# BW1097_TopLevel.net
KiCad netlist of a schematic drawn in Altium Designer
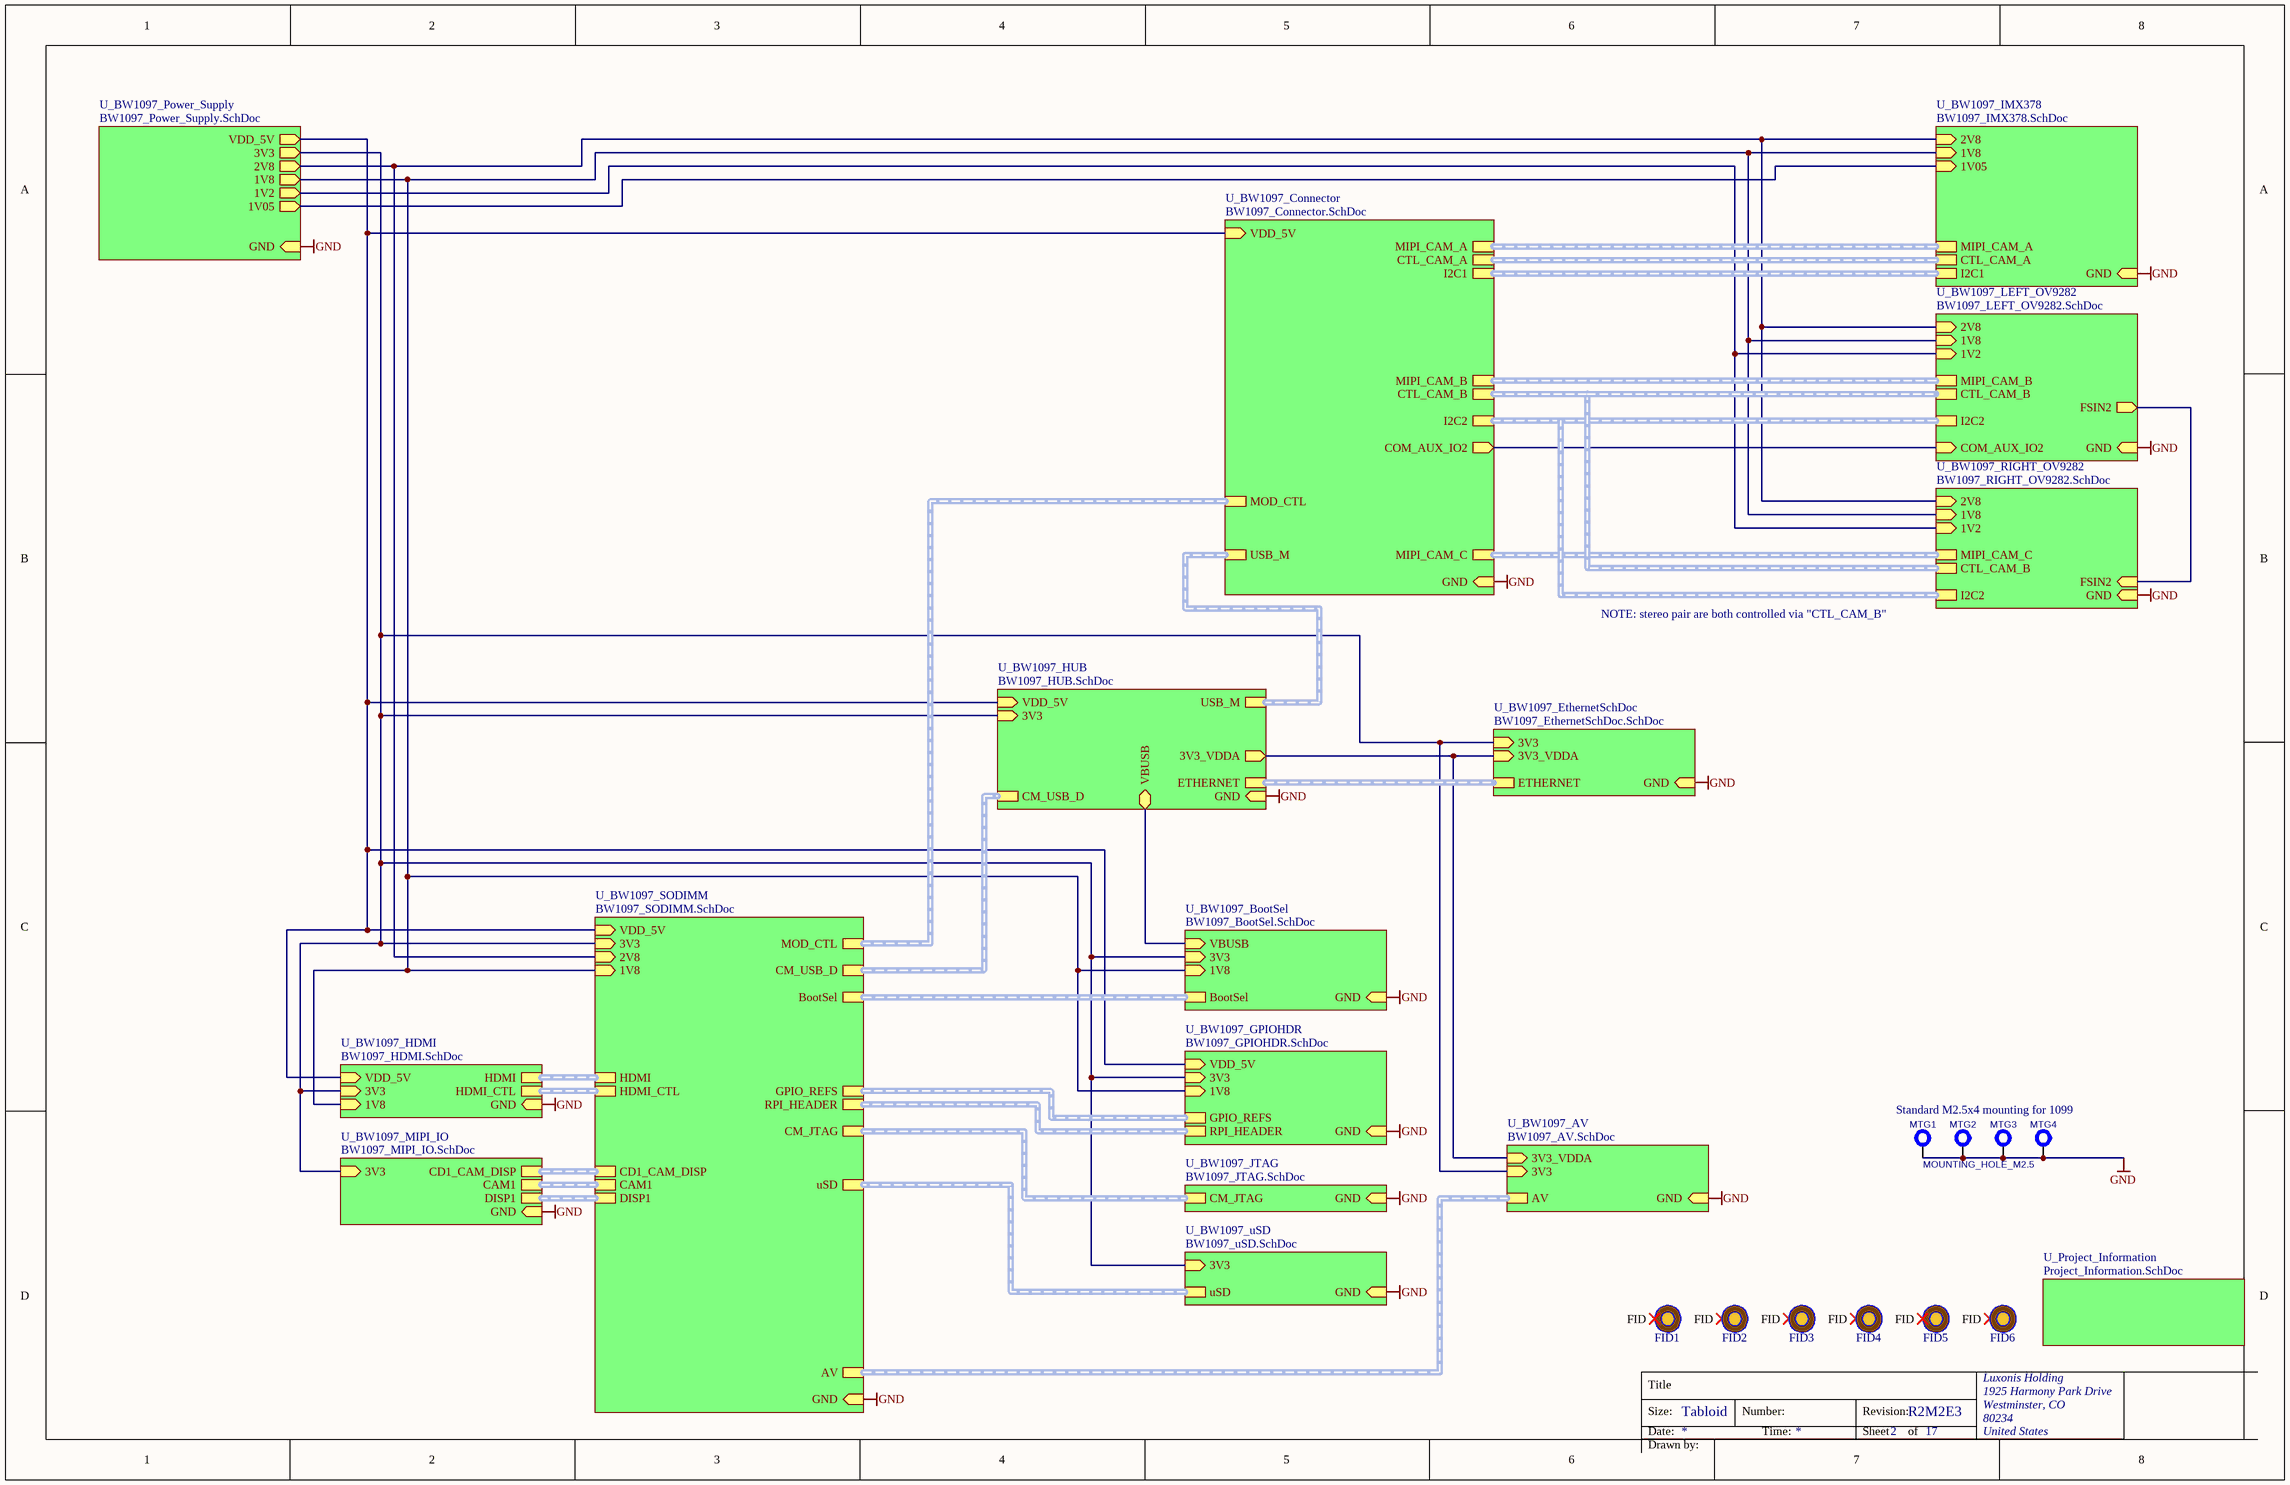
[diagram p0: BW1097_TopLevel.SchDoc]

(export (version "E")
  (design (tool "Eeschema 10.0.6"))
  (components
    (comp (ref "FID1")
      (value "FIDUCIAL_ROUND_1MM")
      (footprint "LuxonisMaster:FIDUCIAL_ROUND_1MM")
      (description "Fiducial with various available footprints")
      (libsource (lib "LuxonisMaster") (part "FIDUCIAL"))
    )
    (comp (ref "FID2")
      (value "FIDUCIAL_ROUND_1MM")
      (footprint "LuxonisMaster:FIDUCIAL_ROUND_1MM")
      (description "Fiducial with various available footprints")
      (libsource (lib "LuxonisMaster") (part "FIDUCIAL"))
    )
    (comp (ref "FID3")
      (value "FIDUCIAL_ROUND_1MM")
      (footprint "LuxonisMaster:FIDUCIAL_ROUND_1MM")
      (description "Fiducial with various available footprints")
      (libsource (lib "LuxonisMaster") (part "FIDUCIAL"))
    )
    (comp (ref "FID4")
      (value "FIDUCIAL_ROUND_1MM")
      (footprint "LuxonisMaster:FIDUCIAL_ROUND_1MM")
      (description "Fiducial with various available footprints")
      (libsource (lib "LuxonisMaster") (part "FIDUCIAL"))
    )
    (comp (ref "FID5")
      (value "FIDUCIAL_ROUND_1MM")
      (footprint "LuxonisMaster:FIDUCIAL_ROUND_1MM")
      (description "Fiducial with various available footprints")
      (libsource (lib "LuxonisMaster") (part "FIDUCIAL"))
    )
    (comp (ref "FID6")
      (value "FIDUCIAL_ROUND_1MM")
      (footprint "LuxonisMaster:FIDUCIAL_ROUND_1MM")
      (description "Fiducial with various available footprints")
      (libsource (lib "LuxonisMaster") (part "FIDUCIAL"))
    )
    (comp (ref "MTG1")
      (value "MOUNTING_HOLE_M2.5")
      (footprint "LuxonisMaster:MOUNTING_HOLE_M2.5")
      (description "=CurrentFootprint")
      (libsource (lib "LuxonisMaster") (part "MP_Mounting-Holes"))
    )
    (comp (ref "MTG2")
      (value "MOUNTING_HOLE_M2.5")
      (footprint "LuxonisMaster:MOUNTING_HOLE_M2.5")
      (description "=CurrentFootprint")
      (libsource (lib "LuxonisMaster") (part "MP_Mounting-Holes"))
    )
    (comp (ref "MTG3")
      (value "MOUNTING_HOLE_M2.5")
      (footprint "LuxonisMaster:MOUNTING_HOLE_M2.5")
      (description "=CurrentFootprint")
      (libsource (lib "LuxonisMaster") (part "MP_Mounting-Holes"))
    )
    (comp (ref "MTG4")
      (value "MOUNTING_HOLE_M2.5")
      (footprint "LuxonisMaster:MOUNTING_HOLE_M2.5")
      (description "=CurrentFootprint")
      (libsource (lib "LuxonisMaster") (part "MP_Mounting-Holes"))
    )
  )
  (nets
    (net (code "33") (name "GND") (class "Default")
      (node (ref "MTG1") (pin "1") (pintype "passive"))
      (node (ref "MTG2") (pin "1") (pintype "passive"))
      (node (ref "MTG3") (pin "1") (pintype "passive"))
      (node (ref "MTG4") (pin "1") (pintype "passive"))
    )
    (net (code "34") (name "unconnected-(FID1-PadFID)") (class "Default")
      (node (ref "FID1") (pin "FID") (pinfunction "FID_FID") (pintype "input+no_connect"))
    )
    (net (code "35") (name "unconnected-(FID2-PadFID)") (class "Default")
      (node (ref "FID2") (pin "FID") (pinfunction "FID_FID") (pintype "input+no_connect"))
    )
    (net (code "36") (name "unconnected-(FID3-PadFID)") (class "Default")
      (node (ref "FID3") (pin "FID") (pinfunction "FID_FID") (pintype "input+no_connect"))
    )
    (net (code "37") (name "unconnected-(FID4-PadFID)") (class "Default")
      (node (ref "FID4") (pin "FID") (pinfunction "FID_FID") (pintype "input+no_connect"))
    )
    (net (code "38") (name "unconnected-(FID5-PadFID)") (class "Default")
      (node (ref "FID5") (pin "FID") (pinfunction "FID_FID") (pintype "input+no_connect"))
    )
    (net (code "39") (name "unconnected-(FID6-PadFID)") (class "Default")
      (node (ref "FID6") (pin "FID") (pinfunction "FID_FID") (pintype "input+no_connect"))
    )
  )
)
